# DebugBreakout_RevD.net
KiCad netlist of a schematic drawn in Altium Designer
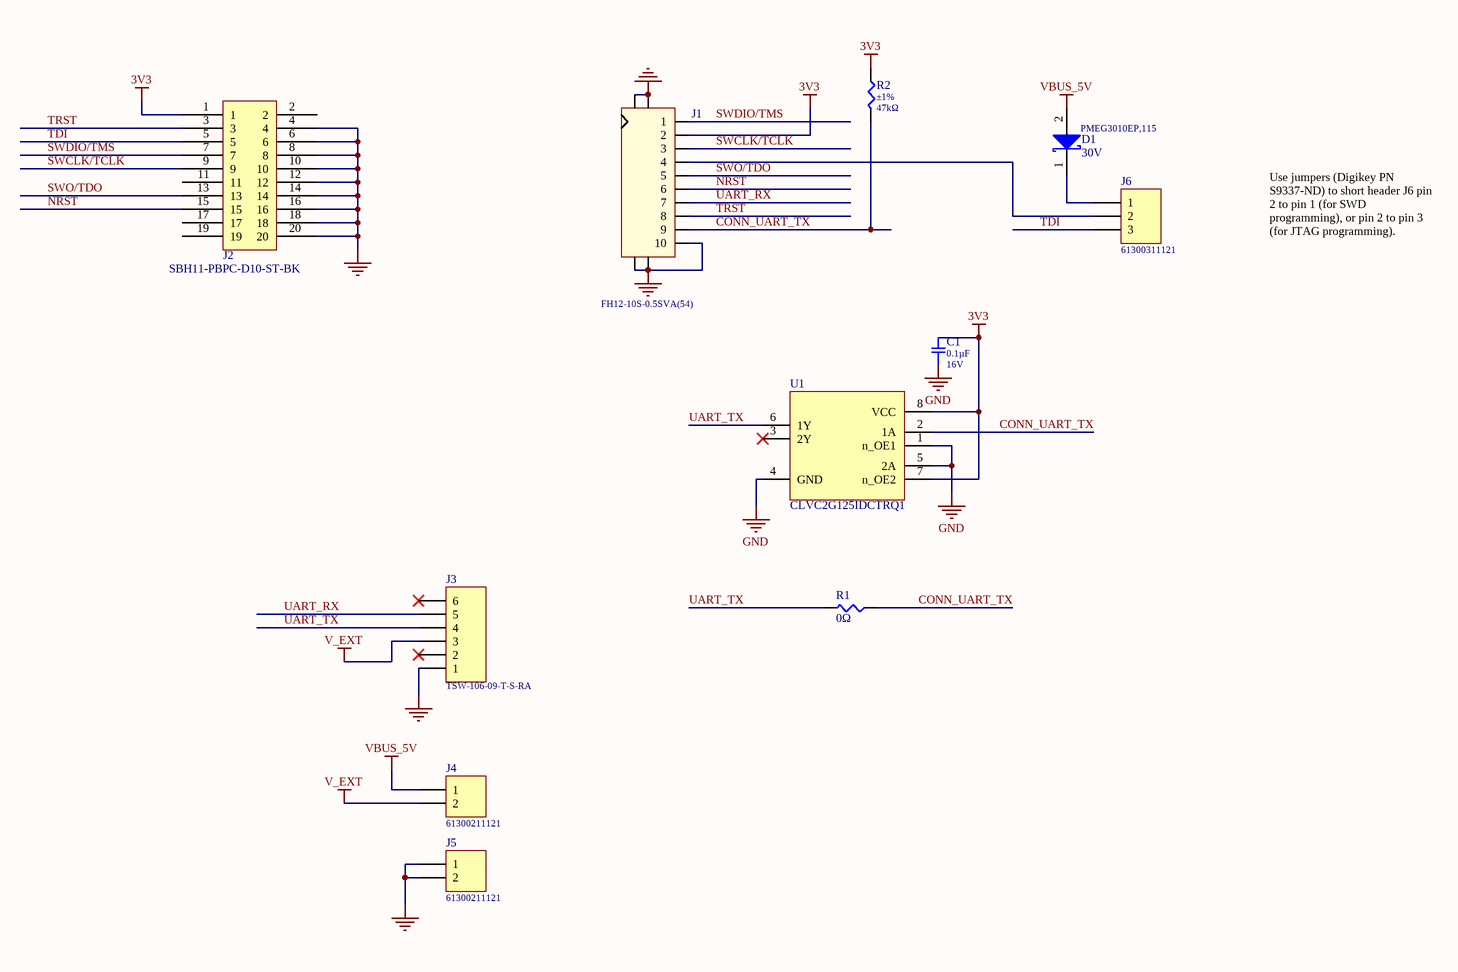
[diagram p0: DebugBreakout_RevD.SchDoc]

(export (version "E")
  (design (tool "Eeschema 10.0.6"))
  (components
    (comp (ref "C1")
      (value "0.1µF")
      (footprint "CAP-0402")
      (description "CAP CER 0.1UF 16V X7R 0402 5%")
      (fields
        (field (name "MANUFACTURER") "Murata")
        (field (name "MPN") "GRM155R71C104JA88D")
        (field (name "VOLTAGE RATING") "16V")
      )
      (libsource (lib "capacitors") (part "CAP-0.1uF-16V-0402"))
    )
    (comp (ref "D1")
      (value "PMEG3010EP,115")
      (footprint "DIODE-SOD128")
      (description "DIODE SCHOTTKY 30V 1A SOD128")
      (fields (field (name "BASE PART NUMBER") "PMEG3010") (field (name "REVERSE VOLTAGE") "30V"))
      (libsource (lib "diodes") (part "DIODE-SCHOTTKY-30V-1A-SOD128"))
    )
    (comp (ref "J1")
      (value "FH12-10S-0.5SVA(54)")
      (footprint "CONN-V-FPC-10P FH12-10S-0.5SVA(54)")
      (description "CONN FFC VERT 10POS 0.50MM SMD")
      (libsource (lib "msx") (part "CONN-V-FPC-10P-0.5MM"))
    )
    (comp (ref "J2")
      (value "SBH11-PBPC-D10-ST-BK")
      (footprint "HDR-V-2x10-KEYED")
      (description "CONN HEADER VERT 20POS 2.54MM")
      (libsource (lib "headers") (part "HDR-V-2x10-M"))
    )
    (comp (ref "J3")
      (value "TSW-106-09-T-S-RA")
      (footprint "HDR-RA-1X6")
      (description "Conn Unshrouded Header HDR 6 POS 2.54mm Solder RA Thru-Hole Automotive Bulk")
      (libsource (lib "headers") (part "HDR-RA-1X6-M"))
    )
    (comp (ref "J4")
      (value "61300211121")
      (footprint "HDR-V-1X2")
      (description "Header, 2-Pin, 0.1\"")
      (fields (field (name "MANUFACTURER") "Wurth Electronics") (field (name "PUBLISHER") "Altium Limited"))
      (libsource (lib "headers") (part "HDR-V-1X2-M"))
    )
    (comp (ref "J5")
      (value "61300211121")
      (footprint "HDR-V-1X2")
      (description "Header, 2-Pin, 0.1\"")
      (fields (field (name "MANUFACTURER") "Wurth Electronics") (field (name "PUBLISHER") "Altium Limited"))
      (libsource (lib "headers") (part "HDR-V-1X2-M"))
    )
    (comp (ref "J6")
      (value "61300311121")
      (footprint "HDR-V-1X3")
      (description "Header, 3-Pin, 0.1\"")
      (fields (field (name "MANUFACTURER") "Wurth Electronics") (field (name "PUBLISHER") "Altium Limited"))
      (libsource (lib "headers") (part "HDR-V-1X3-M"))
    )
    (comp (ref "R1")
      (value "0Ω")
      (footprint "RES-0402")
      (description "RES 0 OHM JUMPER 1/16W 0402")
      (fields
        (field (name "MANUFACTURER") "Yageo")
        (field (name "MANUFACTURER PART NUMBER") "RC0402FR-070RL")
      )
      (libsource (lib "resistors") (part "RES-0-0402"))
    )
    (comp (ref "R2")
      (value "47kΩ")
      (footprint "RES-0402")
      (description "RES SMD 47K OHM 1% 1/16W 0402")
      (fields (field (name "TOLERANCE") "±1%") (field (name "Comment") "RC0402FR-0747KL"))
      (libsource (lib "resistors") (part "RES-47K-0402"))
    )
    (comp (ref "U1")
      (value "CLVC2G125IDCTRQ1")
      (footprint "IC-SM8")
      (description "5.5 V SMT Dual Buffer Gate with 3-State Outputs - SM8")
      (libsource (lib "chagan") (part "IC-CLVC2G125I"))
    )
  )
  (nets
    (net (code "1") (name "/CONN_UART_TX") (class "Default")
      (node (ref "J1") (pin "9") (pinfunction "9_9") (pintype "passive"))
      (node (ref "R1") (pin "1") (pinfunction "1_1") (pintype "passive"))
      (node (ref "R2") (pin "2") (pinfunction "2_2") (pintype "passive"))
      (node (ref "U1") (pin "2") (pinfunction "1A_2") (pintype "passive"))
    )
    (net (code "2") (name "/NRST") (class "Default")
      (node (ref "J1") (pin "6") (pinfunction "6_6") (pintype "passive"))
      (node (ref "J2") (pin "15") (pinfunction "15_15") (pintype "power_in"))
    )
    (net (code "3") (name "/SWCLK{slash}TCLK") (class "Default")
      (node (ref "J1") (pin "3") (pinfunction "3_3") (pintype "passive"))
      (node (ref "J2") (pin "9") (pinfunction "9_9") (pintype "passive"))
    )
    (net (code "4") (name "/SWDIO{slash}TMS") (class "Default")
      (node (ref "J1") (pin "1") (pinfunction "1_1") (pintype "passive"))
      (node (ref "J2") (pin "7") (pinfunction "7_7") (pintype "passive"))
    )
    (net (code "5") (name "/SWO{slash}TDO") (class "Default")
      (node (ref "J1") (pin "5") (pinfunction "5_5") (pintype "passive"))
      (node (ref "J2") (pin "13") (pinfunction "13_13") (pintype "power_in"))
    )
    (net (code "6") (name "/TDI") (class "Default")
      (node (ref "J2") (pin "5") (pinfunction "5_5") (pintype "passive"))
      (node (ref "J6") (pin "3") (pinfunction "3_3") (pintype "passive"))
    )
    (net (code "7") (name "/TRST") (class "Default")
      (node (ref "J1") (pin "8") (pinfunction "8_8") (pintype "passive"))
      (node (ref "J2") (pin "3") (pinfunction "3_3") (pintype "passive"))
    )
    (net (code "8") (name "/UART_RX") (class "Default")
      (node (ref "J1") (pin "7") (pinfunction "7_7") (pintype "passive"))
      (node (ref "J3") (pin "5") (pinfunction "5_5") (pintype "passive"))
    )
    (net (code "9") (name "/UART_TX") (class "Default")
      (node (ref "J3") (pin "4") (pinfunction "4_4") (pintype "passive"))
      (node (ref "R1") (pin "2") (pinfunction "2_2") (pintype "passive"))
      (node (ref "U1") (pin "6") (pinfunction "1Y_6") (pintype "passive"))
    )
    (net (code "10") (name "3V3") (class "Default")
      (node (ref "C1") (pin "2") (pinfunction "2_2") (pintype "passive"))
      (node (ref "J1") (pin "2") (pinfunction "2_2") (pintype "passive"))
      (node (ref "J2") (pin "1") (pinfunction "1_1") (pintype "passive"))
      (node (ref "R2") (pin "1") (pinfunction "1_1") (pintype "passive"))
      (node (ref "U1") (pin "7") (pinfunction "n_OE2_7") (pintype "passive"))
      (node (ref "U1") (pin "8") (pinfunction "VCC_8") (pintype "passive"))
    )
    (net (code "11") (name "GND") (class "Default")
      (node (ref "C1") (pin "1") (pinfunction "1_1") (pintype "passive"))
      (node (ref "J1") (pin "10") (pinfunction "10_10") (pintype "passive"))
      (node (ref "J1") (pin "ME1") (pinfunction "ME1_ME1") (pintype "passive"))
      (node (ref "J1") (pin "ME2") (pinfunction "ME2_ME2") (pintype "passive"))
      (node (ref "J1") (pin "ME3") (pinfunction "ME3_ME3") (pintype "passive"))
      (node (ref "J1") (pin "ME4") (pinfunction "ME4_ME4") (pintype "passive"))
      (node (ref "J2") (pin "10") (pinfunction "10_10") (pintype "passive"))
      (node (ref "J2") (pin "12") (pinfunction "12_12") (pintype "power_in"))
      (node (ref "J2") (pin "14") (pinfunction "14_14") (pintype "power_in"))
      (node (ref "J2") (pin "16") (pinfunction "16_16") (pintype "power_in"))
      (node (ref "J2") (pin "18") (pinfunction "18_18") (pintype "power_in"))
      (node (ref "J2") (pin "20") (pinfunction "20_20") (pintype "power_in"))
      (node (ref "J2") (pin "4") (pinfunction "4_4") (pintype "passive"))
      (node (ref "J2") (pin "6") (pinfunction "6_6") (pintype "passive"))
      (node (ref "J2") (pin "8") (pinfunction "8_8") (pintype "passive"))
      (node (ref "J3") (pin "1") (pinfunction "1_1") (pintype "passive"))
      (node (ref "J5") (pin "1") (pinfunction "1_1") (pintype "passive"))
      (node (ref "J5") (pin "2") (pinfunction "2_2") (pintype "passive"))
      (node (ref "U1") (pin "1") (pinfunction "n_OE1_1") (pintype "passive"))
      (node (ref "U1") (pin "4") (pinfunction "GND_4") (pintype "passive"))
      (node (ref "U1") (pin "5") (pinfunction "2A_5") (pintype "passive"))
    )
    (net (code "12") (name "Net-(D1-K)") (class "Default")
      (node (ref "D1") (pin "1") (pinfunction "K_1") (pintype "passive"))
      (node (ref "J6") (pin "1") (pinfunction "1_1") (pintype "passive"))
    )
    (net (code "13") (name "Net-(J1-Pad4)") (class "Default")
      (node (ref "J1") (pin "4") (pinfunction "4_4") (pintype "passive"))
      (node (ref "J6") (pin "2") (pinfunction "2_2") (pintype "passive"))
    )
    (net (code "14") (name "VBUS_5V") (class "Default")
      (node (ref "D1") (pin "2") (pinfunction "A_2") (pintype "passive"))
      (node (ref "J4") (pin "1") (pinfunction "1_1") (pintype "passive"))
    )
    (net (code "15") (name "V_EXT") (class "Default")
      (node (ref "J3") (pin "3") (pinfunction "3_3") (pintype "passive"))
      (node (ref "J4") (pin "2") (pinfunction "2_2") (pintype "passive"))
    )
    (net (code "16") (name "unconnected-(J2-Pad2)") (class "Default")
      (node (ref "J2") (pin "2") (pinfunction "2_2") (pintype "passive"))
    )
    (net (code "17") (name "unconnected-(J2-Pad11)") (class "Default")
      (node (ref "J2") (pin "11") (pinfunction "11_11") (pintype "power_in"))
    )
    (net (code "18") (name "unconnected-(J2-Pad17)") (class "Default")
      (node (ref "J2") (pin "17") (pinfunction "17_17") (pintype "power_in"))
    )
    (net (code "19") (name "unconnected-(J2-Pad19)") (class "Default")
      (node (ref "J2") (pin "19") (pinfunction "19_19") (pintype "power_in"))
    )
    (net (code "20") (name "unconnected-(J3-Pad2)") (class "Default")
      (node (ref "J3") (pin "2") (pinfunction "2_2") (pintype "passive+no_connect"))
    )
    (net (code "21") (name "unconnected-(J3-Pad6)") (class "Default")
      (node (ref "J3") (pin "6") (pinfunction "6_6") (pintype "passive+no_connect"))
    )
    (net (code "22") (name "unconnected-(U1-2Y-Pad3)") (class "Default")
      (node (ref "U1") (pin "3") (pinfunction "2Y_3") (pintype "passive+no_connect"))
    )
  )
)
